# TFT_Ticketing_Master.net
KiCad netlist of a schematic drawn in Altium Designer
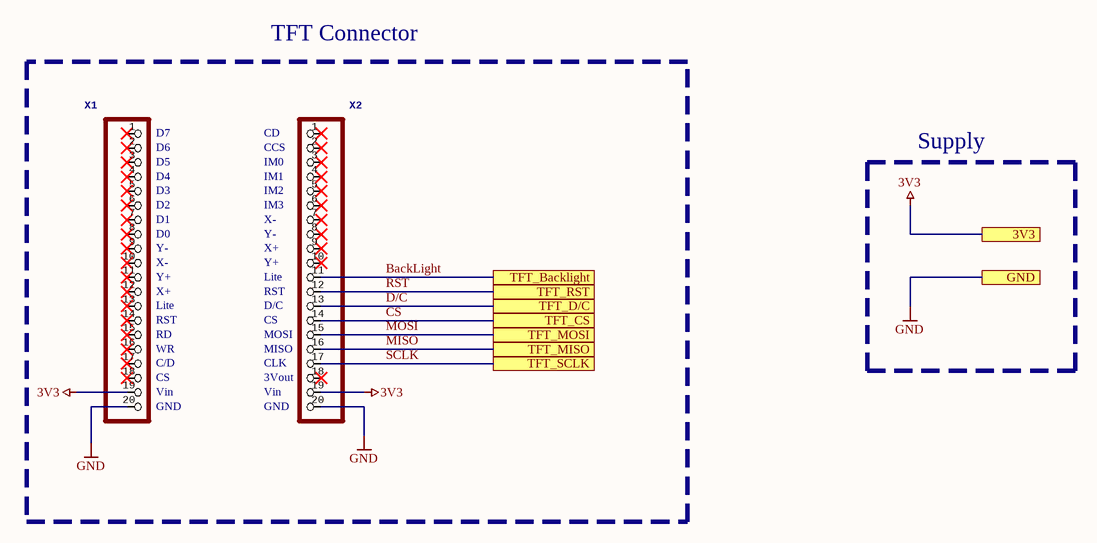
[diagram p0: TFT_Ticketing_Master.SchDoc]

(export (version "E")
  (design (tool "Eeschema 10.0.6"))
  (components
    (comp (ref "X1")
      (value "HEADER-1X20ROUND")
      (footprint "HDR1X20")
      (description "Con_TFT_Gauche")
      (libsource (lib "microbuilder") (part "HEADER-1X20ROUND"))
    )
    (comp (ref "X2")
      (value "HEADER-1X20ROUND")
      (footprint "HDR1X20")
      (description "Con_TFT_Droite")
      (libsource (lib "microbuilder") (part "HEADER-1X20ROUND"))
    )
  )
  (nets
    (net (code "1") (name "/BackLight") (class "Default")
      (node (ref "X2") (pin "11") (pinfunction "11_11") (pintype "passive"))
    )
    (net (code "2") (name "/CS") (class "Default")
      (node (ref "X2") (pin "14") (pinfunction "14_14") (pintype "passive"))
    )
    (net (code "3") (name "/D{slash}C") (class "Default")
      (node (ref "X2") (pin "13") (pinfunction "13_13") (pintype "passive"))
    )
    (net (code "4") (name "/MISO") (class "Default")
      (node (ref "X2") (pin "16") (pinfunction "16_16") (pintype "passive"))
    )
    (net (code "5") (name "/MOSI") (class "Default")
      (node (ref "X2") (pin "15") (pinfunction "15_15") (pintype "passive"))
    )
    (net (code "6") (name "/RST") (class "Default")
      (node (ref "X2") (pin "12") (pinfunction "12_12") (pintype "passive"))
    )
    (net (code "7") (name "/SCLK") (class "Default")
      (node (ref "X2") (pin "17") (pinfunction "17_17") (pintype "passive"))
    )
    (net (code "8") (name "3V3") (class "Default")
      (node (ref "X1") (pin "19") (pinfunction "19_19") (pintype "passive"))
      (node (ref "X2") (pin "19") (pinfunction "19_19") (pintype "passive"))
    )
    (net (code "9") (name "GND") (class "Default")
      (node (ref "X1") (pin "20") (pinfunction "20_20") (pintype "passive"))
      (node (ref "X2") (pin "20") (pinfunction "20_20") (pintype "passive"))
    )
    (net (code "10") (name "unconnected-(X1-Pad1)") (class "Default")
      (node (ref "X1") (pin "1") (pinfunction "1_1") (pintype "passive+no_connect"))
    )
    (net (code "11") (name "unconnected-(X1-Pad2)") (class "Default")
      (node (ref "X1") (pin "2") (pinfunction "2_2") (pintype "passive+no_connect"))
    )
    (net (code "12") (name "unconnected-(X1-Pad3)") (class "Default")
      (node (ref "X1") (pin "3") (pinfunction "3_3") (pintype "passive+no_connect"))
    )
    (net (code "13") (name "unconnected-(X1-Pad4)") (class "Default")
      (node (ref "X1") (pin "4") (pinfunction "4_4") (pintype "passive+no_connect"))
    )
    (net (code "14") (name "unconnected-(X1-Pad5)") (class "Default")
      (node (ref "X1") (pin "5") (pinfunction "5_5") (pintype "passive+no_connect"))
    )
    (net (code "15") (name "unconnected-(X1-Pad6)") (class "Default")
      (node (ref "X1") (pin "6") (pinfunction "6_6") (pintype "passive+no_connect"))
    )
    (net (code "16") (name "unconnected-(X1-Pad7)") (class "Default")
      (node (ref "X1") (pin "7") (pinfunction "7_7") (pintype "passive+no_connect"))
    )
    (net (code "17") (name "unconnected-(X1-Pad8)") (class "Default")
      (node (ref "X1") (pin "8") (pinfunction "8_8") (pintype "passive+no_connect"))
    )
    (net (code "18") (name "unconnected-(X1-Pad9)") (class "Default")
      (node (ref "X1") (pin "9") (pinfunction "9_9") (pintype "passive+no_connect"))
    )
    (net (code "19") (name "unconnected-(X1-Pad10)") (class "Default")
      (node (ref "X1") (pin "10") (pinfunction "10_10") (pintype "passive+no_connect"))
    )
    (net (code "20") (name "unconnected-(X1-Pad11)") (class "Default")
      (node (ref "X1") (pin "11") (pinfunction "11_11") (pintype "passive+no_connect"))
    )
    (net (code "21") (name "unconnected-(X1-Pad12)") (class "Default")
      (node (ref "X1") (pin "12") (pinfunction "12_12") (pintype "passive+no_connect"))
    )
    (net (code "22") (name "unconnected-(X1-Pad13)") (class "Default")
      (node (ref "X1") (pin "13") (pinfunction "13_13") (pintype "passive+no_connect"))
    )
    (net (code "23") (name "unconnected-(X1-Pad14)") (class "Default")
      (node (ref "X1") (pin "14") (pinfunction "14_14") (pintype "passive+no_connect"))
    )
    (net (code "24") (name "unconnected-(X1-Pad15)") (class "Default")
      (node (ref "X1") (pin "15") (pinfunction "15_15") (pintype "passive+no_connect"))
    )
    (net (code "25") (name "unconnected-(X1-Pad16)") (class "Default")
      (node (ref "X1") (pin "16") (pinfunction "16_16") (pintype "passive+no_connect"))
    )
    (net (code "26") (name "unconnected-(X1-Pad17)") (class "Default")
      (node (ref "X1") (pin "17") (pinfunction "17_17") (pintype "passive+no_connect"))
    )
    (net (code "27") (name "unconnected-(X1-Pad18)") (class "Default")
      (node (ref "X1") (pin "18") (pinfunction "18_18") (pintype "passive+no_connect"))
    )
    (net (code "28") (name "unconnected-(X2-Pad1)") (class "Default")
      (node (ref "X2") (pin "1") (pinfunction "1_1") (pintype "passive+no_connect"))
    )
    (net (code "29") (name "unconnected-(X2-Pad2)") (class "Default")
      (node (ref "X2") (pin "2") (pinfunction "2_2") (pintype "passive+no_connect"))
    )
    (net (code "30") (name "unconnected-(X2-Pad3)") (class "Default")
      (node (ref "X2") (pin "3") (pinfunction "3_3") (pintype "passive+no_connect"))
    )
    (net (code "31") (name "unconnected-(X2-Pad4)") (class "Default")
      (node (ref "X2") (pin "4") (pinfunction "4_4") (pintype "passive+no_connect"))
    )
    (net (code "32") (name "unconnected-(X2-Pad5)") (class "Default")
      (node (ref "X2") (pin "5") (pinfunction "5_5") (pintype "passive+no_connect"))
    )
    (net (code "33") (name "unconnected-(X2-Pad6)") (class "Default")
      (node (ref "X2") (pin "6") (pinfunction "6_6") (pintype "passive+no_connect"))
    )
    (net (code "34") (name "unconnected-(X2-Pad7)") (class "Default")
      (node (ref "X2") (pin "7") (pinfunction "7_7") (pintype "passive+no_connect"))
    )
    (net (code "35") (name "unconnected-(X2-Pad8)") (class "Default")
      (node (ref "X2") (pin "8") (pinfunction "8_8") (pintype "passive+no_connect"))
    )
    (net (code "36") (name "unconnected-(X2-Pad9)") (class "Default")
      (node (ref "X2") (pin "9") (pinfunction "9_9") (pintype "passive+no_connect"))
    )
    (net (code "37") (name "unconnected-(X2-Pad10)") (class "Default")
      (node (ref "X2") (pin "10") (pinfunction "10_10") (pintype "passive+no_connect"))
    )
    (net (code "38") (name "unconnected-(X2-Pad18)") (class "Default")
      (node (ref "X2") (pin "18") (pinfunction "18_18") (pintype "passive+no_connect"))
    )
  )
)
